# LEDArray1.net
KiCad netlist of a schematic drawn in EAGLE
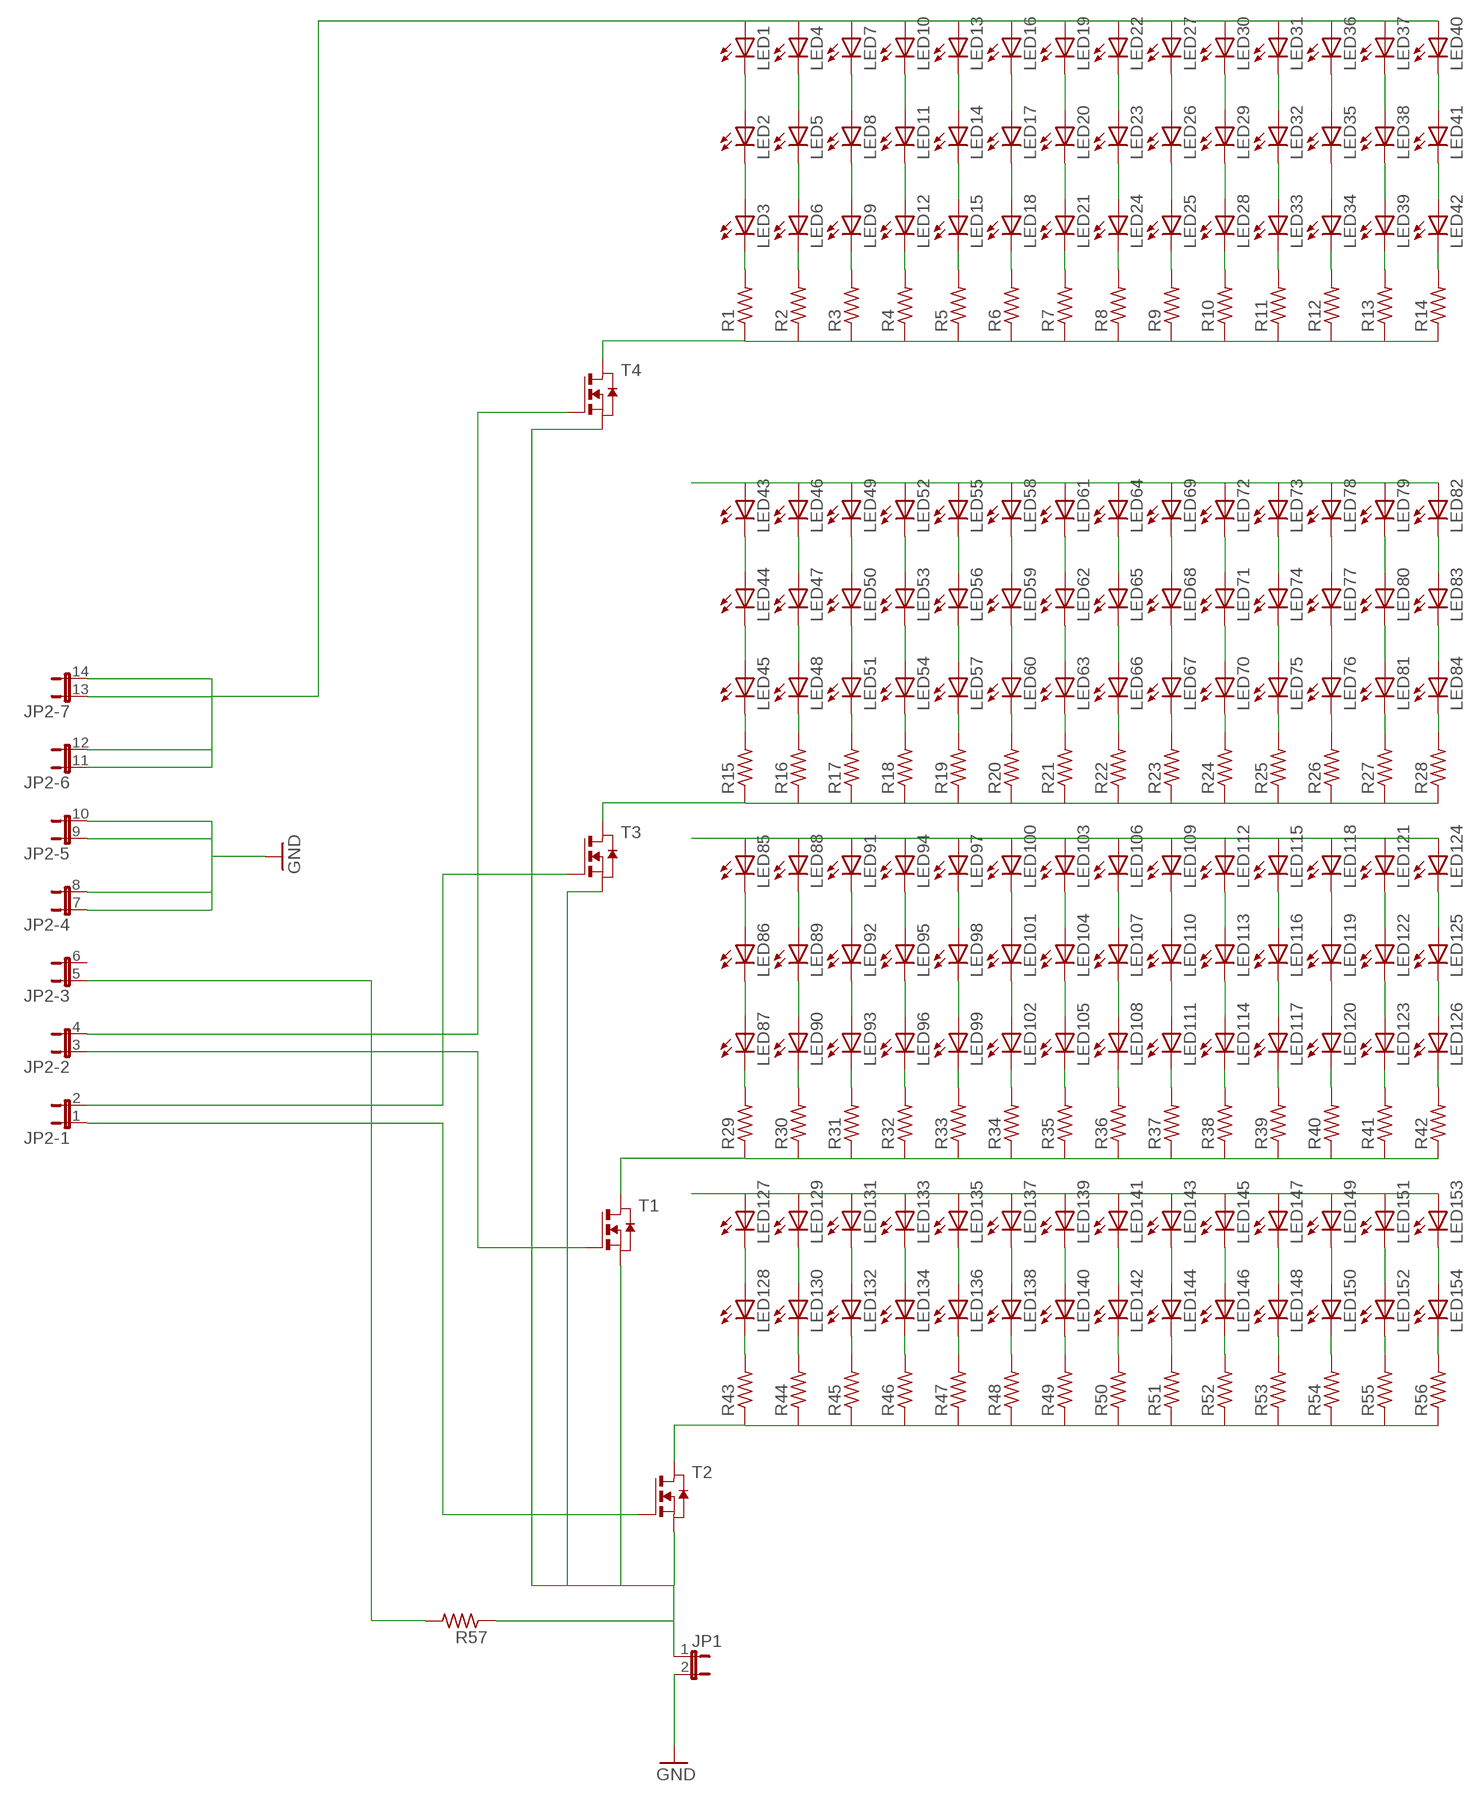
[diagram p0: schematic, sheet 1]

(export (version "E")
  (design (tool "Eeschema 10.0.6"))
  (components
    (comp (ref "JP1")
      (value "JP1E")
      (footprint "eagle-import:JP1")
      (libsource (lib "eagle-import") (part "JP1E"))
    )
    (comp (ref "JP2")
      (value "JP7QE")
      (footprint "eagle-import:JP7Q")
      (libsource (lib "eagle-import") (part "JP7QE"))
    )
    (comp (ref "LED1")
      (value "LED5MM")
      (footprint "eagle-import:LED5MM")
      (libsource (lib "eagle-import") (part "LED5MM"))
    )
    (comp (ref "LED2")
      (value "LED5MM")
      (footprint "eagle-import:LED5MM")
      (libsource (lib "eagle-import") (part "LED5MM"))
    )
    (comp (ref "LED3")
      (value "LED5MM")
      (footprint "eagle-import:LED5MM")
      (libsource (lib "eagle-import") (part "LED5MM"))
    )
    (comp (ref "LED4")
      (value "LED5MM")
      (footprint "eagle-import:LED5MM")
      (libsource (lib "eagle-import") (part "LED5MM"))
    )
    (comp (ref "LED5")
      (value "LED5MM")
      (footprint "eagle-import:LED5MM")
      (libsource (lib "eagle-import") (part "LED5MM"))
    )
    (comp (ref "LED6")
      (value "LED5MM")
      (footprint "eagle-import:LED5MM")
      (libsource (lib "eagle-import") (part "LED5MM"))
    )
    (comp (ref "LED7")
      (value "LED5MM")
      (footprint "eagle-import:LED5MM")
      (libsource (lib "eagle-import") (part "LED5MM"))
    )
    (comp (ref "LED8")
      (value "LED5MM")
      (footprint "eagle-import:LED5MM")
      (libsource (lib "eagle-import") (part "LED5MM"))
    )
    (comp (ref "LED9")
      (value "LED5MM")
      (footprint "eagle-import:LED5MM")
      (libsource (lib "eagle-import") (part "LED5MM"))
    )
    (comp (ref "LED10")
      (value "LED5MM")
      (footprint "eagle-import:LED5MM")
      (libsource (lib "eagle-import") (part "LED5MM"))
    )
    (comp (ref "LED11")
      (value "LED5MM")
      (footprint "eagle-import:LED5MM")
      (libsource (lib "eagle-import") (part "LED5MM"))
    )
    (comp (ref "LED12")
      (value "LED5MM")
      (footprint "eagle-import:LED5MM")
      (libsource (lib "eagle-import") (part "LED5MM"))
    )
    (comp (ref "LED13")
      (value "LED5MM")
      (footprint "eagle-import:LED5MM")
      (libsource (lib "eagle-import") (part "LED5MM"))
    )
    (comp (ref "LED14")
      (value "LED5MM")
      (footprint "eagle-import:LED5MM")
      (libsource (lib "eagle-import") (part "LED5MM"))
    )
    (comp (ref "LED15")
      (value "LED5MM")
      (footprint "eagle-import:LED5MM")
      (libsource (lib "eagle-import") (part "LED5MM"))
    )
    (comp (ref "LED16")
      (value "LED5MM")
      (footprint "eagle-import:LED5MM")
      (libsource (lib "eagle-import") (part "LED5MM"))
    )
    (comp (ref "LED17")
      (value "LED5MM")
      (footprint "eagle-import:LED5MM")
      (libsource (lib "eagle-import") (part "LED5MM"))
    )
    (comp (ref "LED18")
      (value "LED5MM")
      (footprint "eagle-import:LED5MM")
      (libsource (lib "eagle-import") (part "LED5MM"))
    )
    (comp (ref "LED19")
      (value "LED5MM")
      (footprint "eagle-import:LED5MM")
      (libsource (lib "eagle-import") (part "LED5MM"))
    )
    (comp (ref "LED20")
      (value "LED5MM")
      (footprint "eagle-import:LED5MM")
      (libsource (lib "eagle-import") (part "LED5MM"))
    )
    (comp (ref "LED21")
      (value "LED5MM")
      (footprint "eagle-import:LED5MM")
      (libsource (lib "eagle-import") (part "LED5MM"))
    )
    (comp (ref "LED22")
      (value "LED5MM")
      (footprint "eagle-import:LED5MM")
      (libsource (lib "eagle-import") (part "LED5MM"))
    )
    (comp (ref "LED23")
      (value "LED5MM")
      (footprint "eagle-import:LED5MM")
      (libsource (lib "eagle-import") (part "LED5MM"))
    )
    (comp (ref "LED24")
      (value "LED5MM")
      (footprint "eagle-import:LED5MM")
      (libsource (lib "eagle-import") (part "LED5MM"))
    )
    (comp (ref "LED25")
      (value "LED5MM")
      (footprint "eagle-import:LED5MM")
      (libsource (lib "eagle-import") (part "LED5MM"))
    )
    (comp (ref "LED26")
      (value "LED5MM")
      (footprint "eagle-import:LED5MM")
      (libsource (lib "eagle-import") (part "LED5MM"))
    )
    (comp (ref "LED27")
      (value "LED5MM")
      (footprint "eagle-import:LED5MM")
      (libsource (lib "eagle-import") (part "LED5MM"))
    )
    (comp (ref "LED28")
      (value "LED5MM")
      (footprint "eagle-import:LED5MM")
      (libsource (lib "eagle-import") (part "LED5MM"))
    )
    (comp (ref "LED29")
      (value "LED5MM")
      (footprint "eagle-import:LED5MM")
      (libsource (lib "eagle-import") (part "LED5MM"))
    )
    (comp (ref "LED30")
      (value "LED5MM")
      (footprint "eagle-import:LED5MM")
      (libsource (lib "eagle-import") (part "LED5MM"))
    )
    (comp (ref "LED31")
      (value "LED5MM")
      (footprint "eagle-import:LED5MM")
      (libsource (lib "eagle-import") (part "LED5MM"))
    )
    (comp (ref "LED32")
      (value "LED5MM")
      (footprint "eagle-import:LED5MM")
      (libsource (lib "eagle-import") (part "LED5MM"))
    )
    (comp (ref "LED33")
      (value "LED5MM")
      (footprint "eagle-import:LED5MM")
      (libsource (lib "eagle-import") (part "LED5MM"))
    )
    (comp (ref "LED34")
      (value "LED5MM")
      (footprint "eagle-import:LED5MM")
      (libsource (lib "eagle-import") (part "LED5MM"))
    )
    (comp (ref "LED35")
      (value "LED5MM")
      (footprint "eagle-import:LED5MM")
      (libsource (lib "eagle-import") (part "LED5MM"))
    )
    (comp (ref "LED36")
      (value "LED5MM")
      (footprint "eagle-import:LED5MM")
      (libsource (lib "eagle-import") (part "LED5MM"))
    )
    (comp (ref "LED37")
      (value "LED5MM")
      (footprint "eagle-import:LED5MM")
      (libsource (lib "eagle-import") (part "LED5MM"))
    )
    (comp (ref "LED38")
      (value "LED5MM")
      (footprint "eagle-import:LED5MM")
      (libsource (lib "eagle-import") (part "LED5MM"))
    )
    (comp (ref "LED39")
      (value "LED5MM")
      (footprint "eagle-import:LED5MM")
      (libsource (lib "eagle-import") (part "LED5MM"))
    )
    (comp (ref "LED40")
      (value "LED5MM")
      (footprint "eagle-import:LED5MM")
      (libsource (lib "eagle-import") (part "LED5MM"))
    )
    (comp (ref "LED41")
      (value "LED5MM")
      (footprint "eagle-import:LED5MM")
      (libsource (lib "eagle-import") (part "LED5MM"))
    )
    (comp (ref "LED42")
      (value "LED5MM")
      (footprint "eagle-import:LED5MM")
      (libsource (lib "eagle-import") (part "LED5MM"))
    )
    (comp (ref "LED43")
      (value "LED5MM")
      (footprint "eagle-import:LED5MM")
      (libsource (lib "eagle-import") (part "LED5MM"))
    )
    (comp (ref "LED44")
      (value "LED5MM")
      (footprint "eagle-import:LED5MM")
      (libsource (lib "eagle-import") (part "LED5MM"))
    )
    (comp (ref "LED45")
      (value "LED5MM")
      (footprint "eagle-import:LED5MM")
      (libsource (lib "eagle-import") (part "LED5MM"))
    )
    (comp (ref "LED46")
      (value "LED5MM")
      (footprint "eagle-import:LED5MM")
      (libsource (lib "eagle-import") (part "LED5MM"))
    )
    (comp (ref "LED47")
      (value "LED5MM")
      (footprint "eagle-import:LED5MM")
      (libsource (lib "eagle-import") (part "LED5MM"))
    )
    (comp (ref "LED48")
      (value "LED5MM")
      (footprint "eagle-import:LED5MM")
      (libsource (lib "eagle-import") (part "LED5MM"))
    )
    (comp (ref "LED49")
      (value "LED5MM")
      (footprint "eagle-import:LED5MM")
      (libsource (lib "eagle-import") (part "LED5MM"))
    )
    (comp (ref "LED50")
      (value "LED5MM")
      (footprint "eagle-import:LED5MM")
      (libsource (lib "eagle-import") (part "LED5MM"))
    )
    (comp (ref "LED51")
      (value "LED5MM")
      (footprint "eagle-import:LED5MM")
      (libsource (lib "eagle-import") (part "LED5MM"))
    )
    (comp (ref "LED52")
      (value "LED5MM")
      (footprint "eagle-import:LED5MM")
      (libsource (lib "eagle-import") (part "LED5MM"))
    )
    (comp (ref "LED53")
      (value "LED5MM")
      (footprint "eagle-import:LED5MM")
      (libsource (lib "eagle-import") (part "LED5MM"))
    )
    (comp (ref "LED54")
      (value "LED5MM")
      (footprint "eagle-import:LED5MM")
      (libsource (lib "eagle-import") (part "LED5MM"))
    )
    (comp (ref "LED55")
      (value "LED5MM")
      (footprint "eagle-import:LED5MM")
      (libsource (lib "eagle-import") (part "LED5MM"))
    )
    (comp (ref "LED56")
      (value "LED5MM")
      (footprint "eagle-import:LED5MM")
      (libsource (lib "eagle-import") (part "LED5MM"))
    )
    (comp (ref "LED57")
      (value "LED5MM")
      (footprint "eagle-import:LED5MM")
      (libsource (lib "eagle-import") (part "LED5MM"))
    )
    (comp (ref "LED58")
      (value "LED5MM")
      (footprint "eagle-import:LED5MM")
      (libsource (lib "eagle-import") (part "LED5MM"))
    )
    (comp (ref "LED59")
      (value "LED5MM")
      (footprint "eagle-import:LED5MM")
      (libsource (lib "eagle-import") (part "LED5MM"))
    )
    (comp (ref "LED60")
      (value "LED5MM")
      (footprint "eagle-import:LED5MM")
      (libsource (lib "eagle-import") (part "LED5MM"))
    )
    (comp (ref "LED61")
      (value "LED5MM")
      (footprint "eagle-import:LED5MM")
      (libsource (lib "eagle-import") (part "LED5MM"))
    )
    (comp (ref "LED62")
      (value "LED5MM")
      (footprint "eagle-import:LED5MM")
      (libsource (lib "eagle-import") (part "LED5MM"))
    )
    (comp (ref "LED63")
      (value "LED5MM")
      (footprint "eagle-import:LED5MM")
      (libsource (lib "eagle-import") (part "LED5MM"))
    )
    (comp (ref "LED64")
      (value "LED5MM")
      (footprint "eagle-import:LED5MM")
      (libsource (lib "eagle-import") (part "LED5MM"))
    )
    (comp (ref "LED65")
      (value "LED5MM")
      (footprint "eagle-import:LED5MM")
      (libsource (lib "eagle-import") (part "LED5MM"))
    )
    (comp (ref "LED66")
      (value "LED5MM")
      (footprint "eagle-import:LED5MM")
      (libsource (lib "eagle-import") (part "LED5MM"))
    )
    (comp (ref "LED67")
      (value "LED5MM")
      (footprint "eagle-import:LED5MM")
      (libsource (lib "eagle-import") (part "LED5MM"))
    )
    (comp (ref "LED68")
      (value "LED5MM")
      (footprint "eagle-import:LED5MM")
      (libsource (lib "eagle-import") (part "LED5MM"))
    )
    (comp (ref "LED69")
      (value "LED5MM")
      (footprint "eagle-import:LED5MM")
      (libsource (lib "eagle-import") (part "LED5MM"))
    )
    (comp (ref "LED70")
      (value "LED5MM")
      (footprint "eagle-import:LED5MM")
      (libsource (lib "eagle-import") (part "LED5MM"))
    )
    (comp (ref "LED71")
      (value "LED5MM")
      (footprint "eagle-import:LED5MM")
      (libsource (lib "eagle-import") (part "LED5MM"))
    )
    (comp (ref "LED72")
      (value "LED5MM")
      (footprint "eagle-import:LED5MM")
      (libsource (lib "eagle-import") (part "LED5MM"))
    )
    (comp (ref "LED73")
      (value "LED5MM")
      (footprint "eagle-import:LED5MM")
      (libsource (lib "eagle-import") (part "LED5MM"))
    )
    (comp (ref "LED74")
      (value "LED5MM")
      (footprint "eagle-import:LED5MM")
      (libsource (lib "eagle-import") (part "LED5MM"))
    )
    (comp (ref "LED75")
      (value "LED5MM")
      (footprint "eagle-import:LED5MM")
      (libsource (lib "eagle-import") (part "LED5MM"))
    )
    (comp (ref "LED76")
      (value "LED5MM")
      (footprint "eagle-import:LED5MM")
      (libsource (lib "eagle-import") (part "LED5MM"))
    )
    (comp (ref "LED77")
      (value "LED5MM")
      (footprint "eagle-import:LED5MM")
      (libsource (lib "eagle-import") (part "LED5MM"))
    )
    (comp (ref "LED78")
      (value "LED5MM")
      (footprint "eagle-import:LED5MM")
      (libsource (lib "eagle-import") (part "LED5MM"))
    )
    (comp (ref "LED79")
      (value "LED5MM")
      (footprint "eagle-import:LED5MM")
      (libsource (lib "eagle-import") (part "LED5MM"))
    )
    (comp (ref "LED80")
      (value "LED5MM")
      (footprint "eagle-import:LED5MM")
      (libsource (lib "eagle-import") (part "LED5MM"))
    )
    (comp (ref "LED81")
      (value "LED5MM")
      (footprint "eagle-import:LED5MM")
      (libsource (lib "eagle-import") (part "LED5MM"))
    )
    (comp (ref "LED82")
      (value "LED5MM")
      (footprint "eagle-import:LED5MM")
      (libsource (lib "eagle-import") (part "LED5MM"))
    )
    (comp (ref "LED83")
      (value "LED5MM")
      (footprint "eagle-import:LED5MM")
      (libsource (lib "eagle-import") (part "LED5MM"))
    )
    (comp (ref "LED84")
      (value "LED5MM")
      (footprint "eagle-import:LED5MM")
      (libsource (lib "eagle-import") (part "LED5MM"))
    )
    (comp (ref "LED85")
      (value "LED5MM")
      (footprint "eagle-import:LED5MM")
      (libsource (lib "eagle-import") (part "LED5MM"))
    )
    (comp (ref "LED86")
      (value "LED5MM")
      (footprint "eagle-import:LED5MM")
      (libsource (lib "eagle-import") (part "LED5MM"))
    )
    (comp (ref "LED87")
      (value "LED5MM")
      (footprint "eagle-import:LED5MM")
      (libsource (lib "eagle-import") (part "LED5MM"))
    )
    (comp (ref "LED88")
      (value "LED5MM")
      (footprint "eagle-import:LED5MM")
      (libsource (lib "eagle-import") (part "LED5MM"))
    )
    (comp (ref "LED89")
      (value "LED5MM")
      (footprint "eagle-import:LED5MM")
      (libsource (lib "eagle-import") (part "LED5MM"))
    )
    (comp (ref "LED90")
      (value "LED5MM")
      (footprint "eagle-import:LED5MM")
      (libsource (lib "eagle-import") (part "LED5MM"))
    )
    (comp (ref "LED91")
      (value "LED5MM")
      (footprint "eagle-import:LED5MM")
      (libsource (lib "eagle-import") (part "LED5MM"))
    )
    (comp (ref "LED92")
      (value "LED5MM")
      (footprint "eagle-import:LED5MM")
      (libsource (lib "eagle-import") (part "LED5MM"))
    )
    (comp (ref "LED93")
      (value "LED5MM")
      (footprint "eagle-import:LED5MM")
      (libsource (lib "eagle-import") (part "LED5MM"))
    )
    (comp (ref "LED94")
      (value "LED5MM")
      (footprint "eagle-import:LED5MM")
      (libsource (lib "eagle-import") (part "LED5MM"))
    )
    (comp (ref "LED95")
      (value "LED5MM")
      (footprint "eagle-import:LED5MM")
      (libsource (lib "eagle-import") (part "LED5MM"))
    )
    (comp (ref "LED96")
      (value "LED5MM")
      (footprint "eagle-import:LED5MM")
      (libsource (lib "eagle-import") (part "LED5MM"))
    )
    (comp (ref "LED97")
      (value "LED5MM")
      (footprint "eagle-import:LED5MM")
      (libsource (lib "eagle-import") (part "LED5MM"))
    )
    (comp (ref "LED98")
      (value "LED5MM")
      (footprint "eagle-import:LED5MM")
      (libsource (lib "eagle-import") (part "LED5MM"))
    )
    (comp (ref "LED99")
      (value "LED5MM")
      (footprint "eagle-import:LED5MM")
      (libsource (lib "eagle-import") (part "LED5MM"))
    )
    (comp (ref "LED100")
      (value "LED5MM")
      (footprint "eagle-import:LED5MM")
      (libsource (lib "eagle-import") (part "LED5MM"))
    )
    (comp (ref "LED101")
      (value "LED5MM")
      (footprint "eagle-import:LED5MM")
      (libsource (lib "eagle-import") (part "LED5MM"))
    )
    (comp (ref "LED102")
      (value "LED5MM")
      (footprint "eagle-import:LED5MM")
      (libsource (lib "eagle-import") (part "LED5MM"))
    )
    (comp (ref "LED103")
      (value "LED5MM")
      (footprint "eagle-import:LED5MM")
      (libsource (lib "eagle-import") (part "LED5MM"))
    )
    (comp (ref "LED104")
      (value "LED5MM")
      (footprint "eagle-import:LED5MM")
      (libsource (lib "eagle-import") (part "LED5MM"))
    )
    (comp (ref "LED105")
      (value "LED5MM")
      (footprint "eagle-import:LED5MM")
      (libsource (lib "eagle-import") (part "LED5MM"))
    )
    (comp (ref "LED106")
      (value "LED5MM")
      (footprint "eagle-import:LED5MM")
      (libsource (lib "eagle-import") (part "LED5MM"))
    )
    (comp (ref "LED107")
      (value "LED5MM")
      (footprint "eagle-import:LED5MM")
      (libsource (lib "eagle-import") (part "LED5MM"))
    )
    (comp (ref "LED108")
      (value "LED5MM")
      (footprint "eagle-import:LED5MM")
      (libsource (lib "eagle-import") (part "LED5MM"))
    )
    (comp (ref "LED109")
      (value "LED5MM")
      (footprint "eagle-import:LED5MM")
      (libsource (lib "eagle-import") (part "LED5MM"))
    )
    (comp (ref "LED110")
      (value "LED5MM")
      (footprint "eagle-import:LED5MM")
      (libsource (lib "eagle-import") (part "LED5MM"))
    )
    (comp (ref "LED111")
      (value "LED5MM")
      (footprint "eagle-import:LED5MM")
      (libsource (lib "eagle-import") (part "LED5MM"))
    )
    (comp (ref "LED112")
      (value "LED5MM")
      (footprint "eagle-import:LED5MM")
      (libsource (lib "eagle-import") (part "LED5MM"))
    )
    (comp (ref "LED113")
      (value "LED5MM")
      (footprint "eagle-import:LED5MM")
      (libsource (lib "eagle-import") (part "LED5MM"))
    )
    (comp (ref "LED114")
      (value "LED5MM")
      (footprint "eagle-import:LED5MM")
      (libsource (lib "eagle-import") (part "LED5MM"))
    )
    (comp (ref "LED115")
      (value "LED5MM")
      (footprint "eagle-import:LED5MM")
      (libsource (lib "eagle-import") (part "LED5MM"))
    )
    (comp (ref "LED116")
      (value "LED5MM")
      (footprint "eagle-import:LED5MM")
      (libsource (lib "eagle-import") (part "LED5MM"))
    )
    (comp (ref "LED117")
      (value "LED5MM")
      (footprint "eagle-import:LED5MM")
      (libsource (lib "eagle-import") (part "LED5MM"))
    )
    (comp (ref "LED118")
      (value "LED5MM")
      (footprint "eagle-import:LED5MM")
      (libsource (lib "eagle-import") (part "LED5MM"))
    )
    (comp (ref "LED119")
      (value "LED5MM")
      (footprint "eagle-import:LED5MM")
      (libsource (lib "eagle-import") (part "LED5MM"))
    )
    (comp (ref "LED120")
      (value "LED5MM")
      (footprint "eagle-import:LED5MM")
      (libsource (lib "eagle-import") (part "LED5MM"))
    )
    (comp (ref "LED121")
      (value "LED5MM")
      (footprint "eagle-import:LED5MM")
      (libsource (lib "eagle-import") (part "LED5MM"))
    )
    (comp (ref "LED122")
      (value "LED5MM")
      (footprint "eagle-import:LED5MM")
      (libsource (lib "eagle-import") (part "LED5MM"))
    )
    (comp (ref "LED123")
      (value "LED5MM")
      (footprint "eagle-import:LED5MM")
      (libsource (lib "eagle-import") (part "LED5MM"))
    )
    (comp (ref "LED124")
      (value "LED5MM")
      (footprint "eagle-import:LED5MM")
      (libsource (lib "eagle-import") (part "LED5MM"))
    )
    (comp (ref "LED125")
      (value "LED5MM")
      (footprint "eagle-import:LED5MM")
      (libsource (lib "eagle-import") (part "LED5MM"))
    )
    (comp (ref "LED126")
      (value "LED5MM")
      (footprint "eagle-import:LED5MM")
      (libsource (lib "eagle-import") (part "LED5MM"))
    )
    (comp (ref "LED127")
      (value "LED5MM")
      (footprint "eagle-import:LED5MM")
      (libsource (lib "eagle-import") (part "LED5MM"))
    )
    (comp (ref "LED128")
      (value "LED5MM")
      (footprint "eagle-import:LED5MM")
      (libsource (lib "eagle-import") (part "LED5MM"))
    )
    (comp (ref "LED129")
      (value "LED5MM")
      (footprint "eagle-import:LED5MM")
      (libsource (lib "eagle-import") (part "LED5MM"))
    )
    (comp (ref "LED130")
      (value "LED5MM")
      (footprint "eagle-import:LED5MM")
      (libsource (lib "eagle-import") (part "LED5MM"))
    )
    (comp (ref "LED131")
      (value "LED5MM")
      (footprint "eagle-import:LED5MM")
      (libsource (lib "eagle-import") (part "LED5MM"))
    )
    (comp (ref "LED132")
      (value "LED5MM")
      (footprint "eagle-import:LED5MM")
      (libsource (lib "eagle-import") (part "LED5MM"))
    )
    (comp (ref "LED133")
      (value "LED5MM")
      (footprint "eagle-import:LED5MM")
      (libsource (lib "eagle-import") (part "LED5MM"))
    )
    (comp (ref "LED134")
      (value "LED5MM")
      (footprint "eagle-import:LED5MM")
      (libsource (lib "eagle-import") (part "LED5MM"))
    )
    (comp (ref "LED135")
      (value "LED5MM")
      (footprint "eagle-import:LED5MM")
      (libsource (lib "eagle-import") (part "LED5MM"))
    )
    (comp (ref "LED136")
      (value "LED5MM")
      (footprint "eagle-import:LED5MM")
      (libsource (lib "eagle-import") (part "LED5MM"))
    )
    (comp (ref "LED137")
      (value "LED5MM")
      (footprint "eagle-import:LED5MM")
      (libsource (lib "eagle-import") (part "LED5MM"))
    )
    (comp (ref "LED138")
      (value "LED5MM")
      (footprint "eagle-import:LED5MM")
      (libsource (lib "eagle-import") (part "LED5MM"))
    )
    (comp (ref "LED139")
      (value "LED5MM")
      (footprint "eagle-import:LED5MM")
      (libsource (lib "eagle-import") (part "LED5MM"))
    )
    (comp (ref "LED140")
      (value "LED5MM")
      (footprint "eagle-import:LED5MM")
      (libsource (lib "eagle-import") (part "LED5MM"))
    )
    (comp (ref "LED141")
      (value "LED5MM")
      (footprint "eagle-import:LED5MM")
      (libsource (lib "eagle-import") (part "LED5MM"))
    )
    (comp (ref "LED142")
      (value "LED5MM")
      (footprint "eagle-import:LED5MM")
      (libsource (lib "eagle-import") (part "LED5MM"))
    )
    (comp (ref "LED143")
      (value "LED5MM")
      (footprint "eagle-import:LED5MM")
      (libsource (lib "eagle-import") (part "LED5MM"))
    )
    (comp (ref "LED144")
      (value "LED5MM")
      (footprint "eagle-import:LED5MM")
      (libsource (lib "eagle-import") (part "LED5MM"))
    )
    (comp (ref "LED145")
      (value "LED5MM")
      (footprint "eagle-import:LED5MM")
      (libsource (lib "eagle-import") (part "LED5MM"))
    )
    (comp (ref "LED146")
      (value "LED5MM")
      (footprint "eagle-import:LED5MM")
      (libsource (lib "eagle-import") (part "LED5MM"))
    )
    (comp (ref "LED147")
      (value "LED5MM")
      (footprint "eagle-import:LED5MM")
      (libsource (lib "eagle-import") (part "LED5MM"))
    )
    (comp (ref "LED148")
      (value "LED5MM")
      (footprint "eagle-import:LED5MM")
      (libsource (lib "eagle-import") (part "LED5MM"))
    )
    (comp (ref "LED149")
      (value "LED5MM")
      (footprint "eagle-import:LED5MM")
      (libsource (lib "eagle-import") (part "LED5MM"))
    )
    (comp (ref "LED150")
      (value "LED5MM")
      (footprint "eagle-import:LED5MM")
      (libsource (lib "eagle-import") (part "LED5MM"))
    )
    (comp (ref "LED151")
      (value "LED5MM")
      (footprint "eagle-import:LED5MM")
      (libsource (lib "eagle-import") (part "LED5MM"))
    )
    (comp (ref "LED152")
      (value "LED5MM")
      (footprint "eagle-import:LED5MM")
      (libsource (lib "eagle-import") (part "LED5MM"))
    )
    (comp (ref "LED153")
      (value "LED5MM")
      (footprint "eagle-import:LED5MM")
      (libsource (lib "eagle-import") (part "LED5MM"))
    )
    (comp (ref "LED154")
      (value "LED5MM")
      (footprint "eagle-import:LED5MM")
      (libsource (lib "eagle-import") (part "LED5MM"))
    )
    (comp (ref "R1")
      (value "R-US_R0805")
      (footprint "eagle-import:R0805")
      (libsource (lib "eagle-import") (part "R-US_R0805"))
    )
    (comp (ref "R2")
      (value "R-US_R0805")
      (footprint "eagle-import:R0805")
      (libsource (lib "eagle-import") (part "R-US_R0805"))
    )
    (comp (ref "R3")
      (value "R-US_R0805")
      (footprint "eagle-import:R0805")
      (libsource (lib "eagle-import") (part "R-US_R0805"))
    )
    (comp (ref "R4")
      (value "R-US_R0805")
      (footprint "eagle-import:R0805")
      (libsource (lib "eagle-import") (part "R-US_R0805"))
    )
    (comp (ref "R5")
      (value "R-US_R0805")
      (footprint "eagle-import:R0805")
      (libsource (lib "eagle-import") (part "R-US_R0805"))
    )
    (comp (ref "R6")
      (value "R-US_R0805")
      (footprint "eagle-import:R0805")
      (libsource (lib "eagle-import") (part "R-US_R0805"))
    )
    (comp (ref "R7")
      (value "R-US_R0805")
      (footprint "eagle-import:R0805")
      (libsource (lib "eagle-import") (part "R-US_R0805"))
    )
    (comp (ref "R8")
      (value "R-US_R0805")
      (footprint "eagle-import:R0805")
      (libsource (lib "eagle-import") (part "R-US_R0805"))
    )
    (comp (ref "R9")
      (value "R-US_R0805")
      (footprint "eagle-import:R0805")
      (libsource (lib "eagle-import") (part "R-US_R0805"))
    )
    (comp (ref "R10")
      (value "R-US_R0805")
      (footprint "eagle-import:R0805")
      (libsource (lib "eagle-import") (part "R-US_R0805"))
    )
    (comp (ref "R11")
      (value "R-US_R0805")
      (footprint "eagle-import:R0805")
      (libsource (lib "eagle-import") (part "R-US_R0805"))
    )
    (comp (ref "R12")
      (value "R-US_R0805")
      (footprint "eagle-import:R0805")
      (libsource (lib "eagle-import") (part "R-US_R0805"))
    )
    (comp (ref "R13")
      (value "R-US_R0805")
      (footprint "eagle-import:R0805")
      (libsource (lib "eagle-import") (part "R-US_R0805"))
    )
    (comp (ref "R14")
      (value "R-US_R0805")
      (footprint "eagle-import:R0805")
      (libsource (lib "eagle-import") (part "R-US_R0805"))
    )
    (comp (ref "R15")
      (value "R-US_R0805")
      (footprint "eagle-import:R0805")
      (libsource (lib "eagle-import") (part "R-US_R0805"))
    )
    (comp (ref "R16")
      (value "R-US_R0805")
      (footprint "eagle-import:R0805")
      (libsource (lib "eagle-import") (part "R-US_R0805"))
    )
    (comp (ref "R17")
      (value "R-US_R0805")
      (footprint "eagle-import:R0805")
      (libsource (lib "eagle-import") (part "R-US_R0805"))
    )
    (comp (ref "R18")
      (value "R-US_R0805")
      (footprint "eagle-import:R0805")
      (libsource (lib "eagle-import") (part "R-US_R0805"))
    )
    (comp (ref "R19")
      (value "R-US_R0805")
      (footprint "eagle-import:R0805")
      (libsource (lib "eagle-import") (part "R-US_R0805"))
    )
    (comp (ref "R20")
      (value "R-US_R0805")
      (footprint "eagle-import:R0805")
      (libsource (lib "eagle-import") (part "R-US_R0805"))
    )
    (comp (ref "R21")
      (value "R-US_R0805")
      (footprint "eagle-import:R0805")
      (libsource (lib "eagle-import") (part "R-US_R0805"))
    )
    (comp (ref "R22")
      (value "R-US_R0805")
      (footprint "eagle-import:R0805")
      (libsource (lib "eagle-import") (part "R-US_R0805"))
    )
    (comp (ref "R23")
      (value "R-US_R0805")
      (footprint "eagle-import:R0805")
      (libsource (lib "eagle-import") (part "R-US_R0805"))
    )
    (comp (ref "R24")
      (value "R-US_R0805")
      (footprint "eagle-import:R0805")
      (libsource (lib "eagle-import") (part "R-US_R0805"))
    )
    (comp (ref "R25")
      (value "R-US_R0805")
      (footprint "eagle-import:R0805")
      (libsource (lib "eagle-import") (part "R-US_R0805"))
    )
    (comp (ref "R26")
      (value "R-US_R0805")
      (footprint "eagle-import:R0805")
      (libsource (lib "eagle-import") (part "R-US_R0805"))
    )
    (comp (ref "R27")
      (value "R-US_R0805")
      (footprint "eagle-import:R0805")
      (libsource (lib "eagle-import") (part "R-US_R0805"))
    )
    (comp (ref "R28")
      (value "R-US_R0805")
      (footprint "eagle-import:R0805")
      (libsource (lib "eagle-import") (part "R-US_R0805"))
    )
    (comp (ref "R29")
      (value "R-US_R0805")
      (footprint "eagle-import:R0805")
      (libsource (lib "eagle-import") (part "R-US_R0805"))
    )
    (comp (ref "R30")
      (value "R-US_R0805")
      (footprint "eagle-import:R0805")
      (libsource (lib "eagle-import") (part "R-US_R0805"))
    )
    (comp (ref "R31")
      (value "R-US_R0805")
      (footprint "eagle-import:R0805")
      (libsource (lib "eagle-import") (part "R-US_R0805"))
    )
    (comp (ref "R32")
      (value "R-US_R0805")
      (footprint "eagle-import:R0805")
      (libsource (lib "eagle-import") (part "R-US_R0805"))
    )
    (comp (ref "R33")
      (value "R-US_R0805")
      (footprint "eagle-import:R0805")
      (libsource (lib "eagle-import") (part "R-US_R0805"))
    )
    (comp (ref "R34")
      (value "R-US_R0805")
      (footprint "eagle-import:R0805")
      (libsource (lib "eagle-import") (part "R-US_R0805"))
    )
    (comp (ref "R35")
      (value "R-US_R0805")
      (footprint "eagle-import:R0805")
      (libsource (lib "eagle-import") (part "R-US_R0805"))
    )
    (comp (ref "R36")
      (value "R-US_R0805")
      (footprint "eagle-import:R0805")
      (libsource (lib "eagle-import") (part "R-US_R0805"))
    )
    (comp (ref "R37")
      (value "R-US_R0805")
      (footprint "eagle-import:R0805")
      (libsource (lib "eagle-import") (part "R-US_R0805"))
    )
    (comp (ref "R38")
      (value "R-US_R0805")
      (footprint "eagle-import:R0805")
      (libsource (lib "eagle-import") (part "R-US_R0805"))
    )
    (comp (ref "R39")
      (value "R-US_R0805")
      (footprint "eagle-import:R0805")
      (libsource (lib "eagle-import") (part "R-US_R0805"))
    )
    (comp (ref "R40")
      (value "R-US_R0805")
      (footprint "eagle-import:R0805")
      (libsource (lib "eagle-import") (part "R-US_R0805"))
    )
    (comp (ref "R41")
      (value "R-US_R0805")
      (footprint "eagle-import:R0805")
      (libsource (lib "eagle-import") (part "R-US_R0805"))
    )
    (comp (ref "R42")
      (value "R-US_R0805")
      (footprint "eagle-import:R0805")
      (libsource (lib "eagle-import") (part "R-US_R0805"))
    )
    (comp (ref "R43")
      (value "R-US_R0805")
      (footprint "eagle-import:R0805")
      (libsource (lib "eagle-import") (part "R-US_R0805"))
    )
    (comp (ref "R44")
      (value "R-US_R0805")
      (footprint "eagle-import:R0805")
      (libsource (lib "eagle-import") (part "R-US_R0805"))
    )
    (comp (ref "R45")
      (value "R-US_R0805")
      (footprint "eagle-import:R0805")
      (libsource (lib "eagle-import") (part "R-US_R0805"))
    )
    (comp (ref "R46")
      (value "R-US_R0805")
      (footprint "eagle-import:R0805")
      (libsource (lib "eagle-import") (part "R-US_R0805"))
    )
    (comp (ref "R47")
      (value "R-US_R0805")
      (footprint "eagle-import:R0805")
      (libsource (lib "eagle-import") (part "R-US_R0805"))
    )
    (comp (ref "R48")
      (value "R-US_R0805")
      (footprint "eagle-import:R0805")
      (libsource (lib "eagle-import") (part "R-US_R0805"))
    )
    (comp (ref "R49")
      (value "R-US_R0805")
      (footprint "eagle-import:R0805")
      (libsource (lib "eagle-import") (part "R-US_R0805"))
    )
    (comp (ref "R50")
      (value "R-US_R0805")
      (footprint "eagle-import:R0805")
      (libsource (lib "eagle-import") (part "R-US_R0805"))
    )
    (comp (ref "R51")
      (value "R-US_R0805")
      (footprint "eagle-import:R0805")
      (libsource (lib "eagle-import") (part "R-US_R0805"))
    )
    (comp (ref "R52")
      (value "R-US_R0805")
      (footprint "eagle-import:R0805")
      (libsource (lib "eagle-import") (part "R-US_R0805"))
    )
    (comp (ref "R53")
      (value "R-US_R0805")
      (footprint "eagle-import:R0805")
      (libsource (lib "eagle-import") (part "R-US_R0805"))
    )
    (comp (ref "R54")
      (value "R-US_R0805")
      (footprint "eagle-import:R0805")
      (libsource (lib "eagle-import") (part "R-US_R0805"))
    )
    (comp (ref "R55")
      (value "R-US_R0805")
      (footprint "eagle-import:R0805")
      (libsource (lib "eagle-import") (part "R-US_R0805"))
    )
    (comp (ref "R56")
      (value "R-US_R0805")
      (footprint "eagle-import:R0805")
      (libsource (lib "eagle-import") (part "R-US_R0805"))
    )
    (comp (ref "R57")
      (value "R-US_R0805")
      (footprint "eagle-import:R0805")
      (libsource (lib "eagle-import") (part "R-US_R0805"))
    )
    (comp (ref "T1")
      (value "NMOSSOT23")
      (footprint "eagle-import:SOT-23")
      (libsource (lib "eagle-import") (part "NMOSSOT23"))
    )
    (comp (ref "T2")
      (value "NMOSSOT23")
      (footprint "eagle-import:SOT-23")
      (libsource (lib "eagle-import") (part "NMOSSOT23"))
    )
    (comp (ref "T3")
      (value "NMOSSOT23")
      (footprint "eagle-import:SOT-23")
      (libsource (lib "eagle-import") (part "NMOSSOT23"))
    )
    (comp (ref "T4")
      (value "NMOSSOT23")
      (footprint "eagle-import:SOT-23")
      (libsource (lib "eagle-import") (part "NMOSSOT23"))
    )
  )
  (nets
    (net (code "1") (name "/VCC") (class "Default")
      (node (ref "JP2") (pin "11") (pinfunction "1_11") (pintype "passive"))
      (node (ref "JP2") (pin "12") (pinfunction "2_12") (pintype "passive"))
      (node (ref "JP2") (pin "13") (pinfunction "1_13") (pintype "passive"))
      (node (ref "JP2") (pin "14") (pinfunction "2_14") (pintype "passive"))
      (node (ref "LED1") (pin "A") (pinfunction "A_A") (pintype "passive"))
      (node (ref "LED10") (pin "A") (pinfunction "A_A") (pintype "passive"))
      (node (ref "LED100") (pin "A") (pinfunction "A_A") (pintype "passive"))
      (node (ref "LED103") (pin "A") (pinfunction "A_A") (pintype "passive"))
      (node (ref "LED106") (pin "A") (pinfunction "A_A") (pintype "passive"))
      (node (ref "LED109") (pin "A") (pinfunction "A_A") (pintype "passive"))
      (node (ref "LED112") (pin "A") (pinfunction "A_A") (pintype "passive"))
      (node (ref "LED115") (pin "A") (pinfunction "A_A") (pintype "passive"))
      (node (ref "LED118") (pin "A") (pinfunction "A_A") (pintype "passive"))
      (node (ref "LED121") (pin "A") (pinfunction "A_A") (pintype "passive"))
      (node (ref "LED124") (pin "A") (pinfunction "A_A") (pintype "passive"))
      (node (ref "LED127") (pin "A") (pinfunction "A_A") (pintype "passive"))
      (node (ref "LED129") (pin "A") (pinfunction "A_A") (pintype "passive"))
      (node (ref "LED13") (pin "A") (pinfunction "A_A") (pintype "passive"))
      (node (ref "LED131") (pin "A") (pinfunction "A_A") (pintype "passive"))
      (node (ref "LED133") (pin "A") (pinfunction "A_A") (pintype "passive"))
      (node (ref "LED135") (pin "A") (pinfunction "A_A") (pintype "passive"))
      (node (ref "LED137") (pin "A") (pinfunction "A_A") (pintype "passive"))
      (node (ref "LED139") (pin "A") (pinfunction "A_A") (pintype "passive"))
      (node (ref "LED141") (pin "A") (pinfunction "A_A") (pintype "passive"))
      (node (ref "LED143") (pin "A") (pinfunction "A_A") (pintype "passive"))
      (node (ref "LED145") (pin "A") (pinfunction "A_A") (pintype "passive"))
      (node (ref "LED147") (pin "A") (pinfunction "A_A") (pintype "passive"))
      (node (ref "LED149") (pin "A") (pinfunction "A_A") (pintype "passive"))
      (node (ref "LED151") (pin "A") (pinfunction "A_A") (pintype "passive"))
      (node (ref "LED153") (pin "A") (pinfunction "A_A") (pintype "passive"))
      (node (ref "LED16") (pin "A") (pinfunction "A_A") (pintype "passive"))
      (node (ref "LED19") (pin "A") (pinfunction "A_A") (pintype "passive"))
      (node (ref "LED22") (pin "A") (pinfunction "A_A") (pintype "passive"))
      (node (ref "LED27") (pin "A") (pinfunction "A_A") (pintype "passive"))
      (node (ref "LED30") (pin "A") (pinfunction "A_A") (pintype "passive"))
      (node (ref "LED31") (pin "A") (pinfunction "A_A") (pintype "passive"))
      (node (ref "LED36") (pin "A") (pinfunction "A_A") (pintype "passive"))
      (node (ref "LED37") (pin "A") (pinfunction "A_A") (pintype "passive"))
      (node (ref "LED4") (pin "A") (pinfunction "A_A") (pintype "passive"))
      (node (ref "LED40") (pin "A") (pinfunction "A_A") (pintype "passive"))
      (node (ref "LED43") (pin "A") (pinfunction "A_A") (pintype "passive"))
      (node (ref "LED46") (pin "A") (pinfunction "A_A") (pintype "passive"))
      (node (ref "LED49") (pin "A") (pinfunction "A_A") (pintype "passive"))
      (node (ref "LED52") (pin "A") (pinfunction "A_A") (pintype "passive"))
      (node (ref "LED55") (pin "A") (pinfunction "A_A") (pintype "passive"))
      (node (ref "LED58") (pin "A") (pinfunction "A_A") (pintype "passive"))
      (node (ref "LED61") (pin "A") (pinfunction "A_A") (pintype "passive"))
      (node (ref "LED64") (pin "A") (pinfunction "A_A") (pintype "passive"))
      (node (ref "LED69") (pin "A") (pinfunction "A_A") (pintype "passive"))
      (node (ref "LED7") (pin "A") (pinfunction "A_A") (pintype "passive"))
      (node (ref "LED72") (pin "A") (pinfunction "A_A") (pintype "passive"))
      (node (ref "LED73") (pin "A") (pinfunction "A_A") (pintype "passive"))
      (node (ref "LED78") (pin "A") (pinfunction "A_A") (pintype "passive"))
      (node (ref "LED79") (pin "A") (pinfunction "A_A") (pintype "passive"))
      (node (ref "LED82") (pin "A") (pinfunction "A_A") (pintype "passive"))
      (node (ref "LED85") (pin "A") (pinfunction "A_A") (pintype "passive"))
      (node (ref "LED88") (pin "A") (pinfunction "A_A") (pintype "passive"))
      (node (ref "LED91") (pin "A") (pinfunction "A_A") (pintype "passive"))
      (node (ref "LED94") (pin "A") (pinfunction "A_A") (pintype "passive"))
      (node (ref "LED97") (pin "A") (pinfunction "A_A") (pintype "passive"))
    )
    (net (code "2") (name "GND") (class "Default")
      (node (ref "JP1") (pin "2") (pinfunction "2_2") (pintype "passive"))
      (node (ref "JP2") (pin "10") (pinfunction "2_10") (pintype "passive"))
      (node (ref "JP2") (pin "7") (pinfunction "1_7") (pintype "passive"))
      (node (ref "JP2") (pin "8") (pinfunction "2_8") (pintype "passive"))
      (node (ref "JP2") (pin "9") (pinfunction "1_9") (pintype "passive"))
    )
    (net (code "3") (name "Net-(JP2B-1)") (class "Default")
      (node (ref "JP2") (pin "3") (pinfunction "1_3") (pintype "passive"))
      (node (ref "T1") (pin "3") (pinfunction "G_3") (pintype "passive"))
    )
    (net (code "4") (name "Net-(JP2B-2)") (class "Default")
      (node (ref "JP2") (pin "4") (pinfunction "2_4") (pintype "passive"))
      (node (ref "T4") (pin "3") (pinfunction "G_3") (pintype "passive"))
    )
    (net (code "5") (name "Net-(JP2C-1)") (class "Default")
      (node (ref "JP2") (pin "5") (pinfunction "1_5") (pintype "passive"))
      (node (ref "R57") (pin "2") (pinfunction "2_2") (pintype "passive"))
    )
    (net (code "6") (name "Net-(LED1-C)") (class "Default")
      (node (ref "LED1") (pin "K") (pinfunction "C_K") (pintype "passive"))
      (node (ref "LED2") (pin "A") (pinfunction "A_A") (pintype "passive"))
    )
    (net (code "7") (name "Net-(LED2-C)") (class "Default")
      (node (ref "LED2") (pin "K") (pinfunction "C_K") (pintype "passive"))
      (node (ref "LED3") (pin "A") (pinfunction "A_A") (pintype "passive"))
    )
    (net (code "8") (name "Net-(LED3-C)") (class "Default")
      (node (ref "LED3") (pin "K") (pinfunction "C_K") (pintype "passive"))
      (node (ref "R1") (pin "2") (pinfunction "2_2") (pintype "passive"))
    )
    (net (code "9") (name "Net-(LED4-C)") (class "Default")
      (node (ref "LED4") (pin "K") (pinfunction "C_K") (pintype "passive"))
      (node (ref "LED5") (pin "A") (pinfunction "A_A") (pintype "passive"))
    )
    (net (code "10") (name "Net-(LED5-C)") (class "Default")
      (node (ref "LED5") (pin "K") (pinfunction "C_K") (pintype "passive"))
      (node (ref "LED6") (pin "A") (pinfunction "A_A") (pintype "passive"))
    )
    (net (code "11") (name "Net-(LED6-C)") (class "Default")
      (node (ref "LED6") (pin "K") (pinfunction "C_K") (pintype "passive"))
      (node (ref "R2") (pin "2") (pinfunction "2_2") (pintype "passive"))
    )
    (net (code "12") (name "Net-(LED7-C)") (class "Default")
      (node (ref "LED7") (pin "K") (pinfunction "C_K") (pintype "passive"))
      (node (ref "LED8") (pin "A") (pinfunction "A_A") (pintype "passive"))
    )
    (net (code "13") (name "Net-(LED8-C)") (class "Default")
      (node (ref "LED8") (pin "K") (pinfunction "C_K") (pintype "passive"))
      (node (ref "LED9") (pin "A") (pinfunction "A_A") (pintype "passive"))
    )
    (net (code "14") (name "Net-(LED9-C)") (class "Default")
      (node (ref "LED9") (pin "K") (pinfunction "C_K") (pintype "passive"))
      (node (ref "R3") (pin "2") (pinfunction "2_2") (pintype "passive"))
    )
    (net (code "15") (name "Net-(LED10-C)") (class "Default")
      (node (ref "LED10") (pin "K") (pinfunction "C_K") (pintype "passive"))
      (node (ref "LED11") (pin "A") (pinfunction "A_A") (pintype "passive"))
    )
    (net (code "16") (name "Net-(LED11-C)") (class "Default")
      (node (ref "LED11") (pin "K") (pinfunction "C_K") (pintype "passive"))
      (node (ref "LED12") (pin "A") (pinfunction "A_A") (pintype "passive"))
    )
    (net (code "17") (name "Net-(LED12-C)") (class "Default")
      (node (ref "LED12") (pin "K") (pinfunction "C_K") (pintype "passive"))
      (node (ref "R4") (pin "2") (pinfunction "2_2") (pintype "passive"))
    )
    (net (code "18") (name "Net-(LED13-C)") (class "Default")
      (node (ref "LED13") (pin "K") (pinfunction "C_K") (pintype "passive"))
      (node (ref "LED14") (pin "A") (pinfunction "A_A") (pintype "passive"))
    )
    (net (code "19") (name "Net-(LED14-C)") (class "Default")
      (node (ref "LED14") (pin "K") (pinfunction "C_K") (pintype "passive"))
      (node (ref "LED15") (pin "A") (pinfunction "A_A") (pintype "passive"))
    )
    (net (code "20") (name "Net-(LED15-C)") (class "Default")
      (node (ref "LED15") (pin "K") (pinfunction "C_K") (pintype "passive"))
      (node (ref "R5") (pin "2") (pinfunction "2_2") (pintype "passive"))
    )
    (net (code "21") (name "Net-(LED16-C)") (class "Default")
      (node (ref "LED16") (pin "K") (pinfunction "C_K") (pintype "passive"))
      (node (ref "LED17") (pin "A") (pinfunction "A_A") (pintype "passive"))
    )
    (net (code "22") (name "Net-(LED17-C)") (class "Default")
      (node (ref "LED17") (pin "K") (pinfunction "C_K") (pintype "passive"))
      (node (ref "LED18") (pin "A") (pinfunction "A_A") (pintype "passive"))
    )
    (net (code "23") (name "Net-(LED18-C)") (class "Default")
      (node (ref "LED18") (pin "K") (pinfunction "C_K") (pintype "passive"))
      (node (ref "R6") (pin "2") (pinfunction "2_2") (pintype "passive"))
    )
    (net (code "24") (name "Net-(LED19-C)") (class "Default")
      (node (ref "LED19") (pin "K") (pinfunction "C_K") (pintype "passive"))
      (node (ref "LED20") (pin "A") (pinfunction "A_A") (pintype "passive"))
    )
    (net (code "25") (name "Net-(LED20-C)") (class "Default")
      (node (ref "LED20") (pin "K") (pinfunction "C_K") (pintype "passive"))
      (node (ref "LED21") (pin "A") (pinfunction "A_A") (pintype "passive"))
    )
    (net (code "26") (name "Net-(LED21-C)") (class "Default")
      (node (ref "LED21") (pin "K") (pinfunction "C_K") (pintype "passive"))
      (node (ref "R7") (pin "2") (pinfunction "2_2") (pintype "passive"))
    )
    (net (code "27") (name "Net-(LED22-C)") (class "Default")
      (node (ref "LED22") (pin "K") (pinfunction "C_K") (pintype "passive"))
      (node (ref "LED23") (pin "A") (pinfunction "A_A") (pintype "passive"))
    )
    (net (code "28") (name "Net-(LED23-C)") (class "Default")
      (node (ref "LED23") (pin "K") (pinfunction "C_K") (pintype "passive"))
      (node (ref "LED24") (pin "A") (pinfunction "A_A") (pintype "passive"))
    )
    (net (code "29") (name "Net-(LED24-C)") (class "Default")
      (node (ref "LED24") (pin "K") (pinfunction "C_K") (pintype "passive"))
      (node (ref "R8") (pin "2") (pinfunction "2_2") (pintype "passive"))
    )
    (net (code "30") (name "Net-(LED25-C)") (class "Default")
      (node (ref "LED25") (pin "K") (pinfunction "C_K") (pintype "passive"))
      (node (ref "R9") (pin "2") (pinfunction "2_2") (pintype "passive"))
    )
    (net (code "31") (name "Net-(LED26-C)") (class "Default")
      (node (ref "LED25") (pin "A") (pinfunction "A_A") (pintype "passive"))
      (node (ref "LED26") (pin "K") (pinfunction "C_K") (pintype "passive"))
    )
    (net (code "32") (name "Net-(LED27-C)") (class "Default")
      (node (ref "LED26") (pin "A") (pinfunction "A_A") (pintype "passive"))
      (node (ref "LED27") (pin "K") (pinfunction "C_K") (pintype "passive"))
    )
    (net (code "33") (name "Net-(LED28-C)") (class "Default")
      (node (ref "LED28") (pin "K") (pinfunction "C_K") (pintype "passive"))
      (node (ref "R10") (pin "2") (pinfunction "2_2") (pintype "passive"))
    )
    (net (code "34") (name "Net-(LED29-C)") (class "Default")
      (node (ref "LED28") (pin "A") (pinfunction "A_A") (pintype "passive"))
      (node (ref "LED29") (pin "K") (pinfunction "C_K") (pintype "passive"))
    )
    (net (code "35") (name "Net-(LED30-C)") (class "Default")
      (node (ref "LED29") (pin "A") (pinfunction "A_A") (pintype "passive"))
      (node (ref "LED30") (pin "K") (pinfunction "C_K") (pintype "passive"))
    )
    (net (code "36") (name "Net-(LED31-C)") (class "Default")
      (node (ref "LED31") (pin "K") (pinfunction "C_K") (pintype "passive"))
      (node (ref "LED32") (pin "A") (pinfunction "A_A") (pintype "passive"))
    )
    (net (code "37") (name "Net-(LED32-C)") (class "Default")
      (node (ref "LED32") (pin "K") (pinfunction "C_K") (pintype "passive"))
      (node (ref "LED33") (pin "A") (pinfunction "A_A") (pintype "passive"))
    )
    (net (code "38") (name "Net-(LED33-C)") (class "Default")
      (node (ref "LED33") (pin "K") (pinfunction "C_K") (pintype "passive"))
      (node (ref "R11") (pin "2") (pinfunction "2_2") (pintype "passive"))
    )
    (net (code "39") (name "Net-(LED34-C)") (class "Default")
      (node (ref "LED34") (pin "K") (pinfunction "C_K") (pintype "passive"))
      (node (ref "R12") (pin "2") (pinfunction "2_2") (pintype "passive"))
    )
    (net (code "40") (name "Net-(LED35-C)") (class "Default")
      (node (ref "LED34") (pin "A") (pinfunction "A_A") (pintype "passive"))
      (node (ref "LED35") (pin "K") (pinfunction "C_K") (pintype "passive"))
    )
    (net (code "41") (name "Net-(LED36-C)") (class "Default")
      (node (ref "LED35") (pin "A") (pinfunction "A_A") (pintype "passive"))
      (node (ref "LED36") (pin "K") (pinfunction "C_K") (pintype "passive"))
    )
    (net (code "42") (name "Net-(LED37-C)") (class "Default")
      (node (ref "LED37") (pin "K") (pinfunction "C_K") (pintype "passive"))
      (node (ref "LED38") (pin "A") (pinfunction "A_A") (pintype "passive"))
    )
    (net (code "43") (name "Net-(LED38-C)") (class "Default")
      (node (ref "LED38") (pin "K") (pinfunction "C_K") (pintype "passive"))
      (node (ref "LED39") (pin "A") (pinfunction "A_A") (pintype "passive"))
    )
    (net (code "44") (name "Net-(LED39-C)") (class "Default")
      (node (ref "LED39") (pin "K") (pinfunction "C_K") (pintype "passive"))
      (node (ref "R13") (pin "2") (pinfunction "2_2") (pintype "passive"))
    )
    (net (code "45") (name "Net-(LED40-C)") (class "Default")
      (node (ref "LED40") (pin "K") (pinfunction "C_K") (pintype "passive"))
      (node (ref "LED41") (pin "A") (pinfunction "A_A") (pintype "passive"))
    )
    (net (code "46") (name "Net-(LED41-C)") (class "Default")
      (node (ref "LED41") (pin "K") (pinfunction "C_K") (pintype "passive"))
      (node (ref "LED42") (pin "A") (pinfunction "A_A") (pintype "passive"))
    )
    (net (code "47") (name "Net-(LED42-C)") (class "Default")
      (node (ref "LED42") (pin "K") (pinfunction "C_K") (pintype "passive"))
      (node (ref "R14") (pin "2") (pinfunction "2_2") (pintype "passive"))
    )
    (net (code "48") (name "Net-(LED43-C)") (class "Default")
      (node (ref "LED43") (pin "K") (pinfunction "C_K") (pintype "passive"))
      (node (ref "LED44") (pin "A") (pinfunction "A_A") (pintype "passive"))
    )
    (net (code "49") (name "Net-(LED44-C)") (class "Default")
      (node (ref "LED44") (pin "K") (pinfunction "C_K") (pintype "passive"))
      (node (ref "LED45") (pin "A") (pinfunction "A_A") (pintype "passive"))
    )
    (net (code "50") (name "Net-(LED45-C)") (class "Default")
      (node (ref "LED45") (pin "K") (pinfunction "C_K") (pintype "passive"))
      (node (ref "R15") (pin "2") (pinfunction "2_2") (pintype "passive"))
    )
    (net (code "51") (name "Net-(LED46-C)") (class "Default")
      (node (ref "LED46") (pin "K") (pinfunction "C_K") (pintype "passive"))
      (node (ref "LED47") (pin "A") (pinfunction "A_A") (pintype "passive"))
    )
    (net (code "52") (name "Net-(LED47-C)") (class "Default")
      (node (ref "LED47") (pin "K") (pinfunction "C_K") (pintype "passive"))
      (node (ref "LED48") (pin "A") (pinfunction "A_A") (pintype "passive"))
    )
    (net (code "53") (name "Net-(LED48-C)") (class "Default")
      (node (ref "LED48") (pin "K") (pinfunction "C_K") (pintype "passive"))
      (node (ref "R16") (pin "2") (pinfunction "2_2") (pintype "passive"))
    )
    (net (code "54") (name "Net-(LED49-C)") (class "Default")
      (node (ref "LED49") (pin "K") (pinfunction "C_K") (pintype "passive"))
      (node (ref "LED50") (pin "A") (pinfunction "A_A") (pintype "passive"))
    )
    (net (code "55") (name "Net-(LED50-C)") (class "Default")
      (node (ref "LED50") (pin "K") (pinfunction "C_K") (pintype "passive"))
      (node (ref "LED51") (pin "A") (pinfunction "A_A") (pintype "passive"))
    )
    (net (code "56") (name "Net-(LED51-C)") (class "Default")
      (node (ref "LED51") (pin "K") (pinfunction "C_K") (pintype "passive"))
      (node (ref "R17") (pin "2") (pinfunction "2_2") (pintype "passive"))
    )
    (net (code "57") (name "Net-(LED52-C)") (class "Default")
      (node (ref "LED52") (pin "K") (pinfunction "C_K") (pintype "passive"))
      (node (ref "LED53") (pin "A") (pinfunction "A_A") (pintype "passive"))
    )
    (net (code "58") (name "Net-(LED53-C)") (class "Default")
      (node (ref "LED53") (pin "K") (pinfunction "C_K") (pintype "passive"))
      (node (ref "LED54") (pin "A") (pinfunction "A_A") (pintype "passive"))
    )
    (net (code "59") (name "Net-(LED54-C)") (class "Default")
      (node (ref "LED54") (pin "K") (pinfunction "C_K") (pintype "passive"))
      (node (ref "R18") (pin "2") (pinfunction "2_2") (pintype "passive"))
    )
    (net (code "60") (name "Net-(LED55-C)") (class "Default")
      (node (ref "LED55") (pin "K") (pinfunction "C_K") (pintype "passive"))
      (node (ref "LED56") (pin "A") (pinfunction "A_A") (pintype "passive"))
    )
    (net (code "61") (name "Net-(LED56-C)") (class "Default")
      (node (ref "LED56") (pin "K") (pinfunction "C_K") (pintype "passive"))
      (node (ref "LED57") (pin "A") (pinfunction "A_A") (pintype "passive"))
    )
    (net (code "62") (name "Net-(LED57-C)") (class "Default")
      (node (ref "LED57") (pin "K") (pinfunction "C_K") (pintype "passive"))
      (node (ref "R19") (pin "2") (pinfunction "2_2") (pintype "passive"))
    )
    (net (code "63") (name "Net-(LED58-C)") (class "Default")
      (node (ref "LED58") (pin "K") (pinfunction "C_K") (pintype "passive"))
      (node (ref "LED59") (pin "A") (pinfunction "A_A") (pintype "passive"))
    )
    (net (code "64") (name "Net-(LED59-C)") (class "Default")
      (node (ref "LED59") (pin "K") (pinfunction "C_K") (pintype "passive"))
      (node (ref "LED60") (pin "A") (pinfunction "A_A") (pintype "passive"))
    )
    (net (code "65") (name "Net-(LED60-C)") (class "Default")
      (node (ref "LED60") (pin "K") (pinfunction "C_K") (pintype "passive"))
      (node (ref "R20") (pin "2") (pinfunction "2_2") (pintype "passive"))
    )
    (net (code "66") (name "Net-(LED61-C)") (class "Default")
      (node (ref "LED61") (pin "K") (pinfunction "C_K") (pintype "passive"))
      (node (ref "LED62") (pin "A") (pinfunction "A_A") (pintype "passive"))
    )
    (net (code "67") (name "Net-(LED62-C)") (class "Default")
      (node (ref "LED62") (pin "K") (pinfunction "C_K") (pintype "passive"))
      (node (ref "LED63") (pin "A") (pinfunction "A_A") (pintype "passive"))
    )
    (net (code "68") (name "Net-(LED63-C)") (class "Default")
      (node (ref "LED63") (pin "K") (pinfunction "C_K") (pintype "passive"))
      (node (ref "R21") (pin "2") (pinfunction "2_2") (pintype "passive"))
    )
    (net (code "69") (name "Net-(LED64-C)") (class "Default")
      (node (ref "LED64") (pin "K") (pinfunction "C_K") (pintype "passive"))
      (node (ref "LED65") (pin "A") (pinfunction "A_A") (pintype "passive"))
    )
    (net (code "70") (name "Net-(LED65-C)") (class "Default")
      (node (ref "LED65") (pin "K") (pinfunction "C_K") (pintype "passive"))
      (node (ref "LED66") (pin "A") (pinfunction "A_A") (pintype "passive"))
    )
    (net (code "71") (name "Net-(LED66-C)") (class "Default")
      (node (ref "LED66") (pin "K") (pinfunction "C_K") (pintype "passive"))
      (node (ref "R22") (pin "2") (pinfunction "2_2") (pintype "passive"))
    )
    (net (code "72") (name "Net-(LED67-C)") (class "Default")
      (node (ref "LED67") (pin "K") (pinfunction "C_K") (pintype "passive"))
      (node (ref "R23") (pin "2") (pinfunction "2_2") (pintype "passive"))
    )
    (net (code "73") (name "Net-(LED68-C)") (class "Default")
      (node (ref "LED67") (pin "A") (pinfunction "A_A") (pintype "passive"))
      (node (ref "LED68") (pin "K") (pinfunction "C_K") (pintype "passive"))
    )
    (net (code "74") (name "Net-(LED69-C)") (class "Default")
      (node (ref "LED68") (pin "A") (pinfunction "A_A") (pintype "passive"))
      (node (ref "LED69") (pin "K") (pinfunction "C_K") (pintype "passive"))
    )
    (net (code "75") (name "Net-(LED70-C)") (class "Default")
      (node (ref "LED70") (pin "K") (pinfunction "C_K") (pintype "passive"))
      (node (ref "R24") (pin "2") (pinfunction "2_2") (pintype "passive"))
    )
    (net (code "76") (name "Net-(LED71-C)") (class "Default")
      (node (ref "LED70") (pin "A") (pinfunction "A_A") (pintype "passive"))
      (node (ref "LED71") (pin "K") (pinfunction "C_K") (pintype "passive"))
    )
    (net (code "77") (name "Net-(LED72-C)") (class "Default")
      (node (ref "LED71") (pin "A") (pinfunction "A_A") (pintype "passive"))
      (node (ref "LED72") (pin "K") (pinfunction "C_K") (pintype "passive"))
    )
    (net (code "78") (name "Net-(LED73-C)") (class "Default")
      (node (ref "LED73") (pin "K") (pinfunction "C_K") (pintype "passive"))
      (node (ref "LED74") (pin "A") (pinfunction "A_A") (pintype "passive"))
    )
    (net (code "79") (name "Net-(LED74-C)") (class "Default")
      (node (ref "LED74") (pin "K") (pinfunction "C_K") (pintype "passive"))
      (node (ref "LED75") (pin "A") (pinfunction "A_A") (pintype "passive"))
    )
    (net (code "80") (name "Net-(LED75-C)") (class "Default")
      (node (ref "LED75") (pin "K") (pinfunction "C_K") (pintype "passive"))
      (node (ref "R25") (pin "2") (pinfunction "2_2") (pintype "passive"))
    )
    (net (code "81") (name "Net-(LED76-C)") (class "Default")
      (node (ref "LED76") (pin "K") (pinfunction "C_K") (pintype "passive"))
      (node (ref "R26") (pin "2") (pinfunction "2_2") (pintype "passive"))
    )
    (net (code "82") (name "Net-(LED77-C)") (class "Default")
      (node (ref "LED76") (pin "A") (pinfunction "A_A") (pintype "passive"))
      (node (ref "LED77") (pin "K") (pinfunction "C_K") (pintype "passive"))
    )
    (net (code "83") (name "Net-(LED78-C)") (class "Default")
      (node (ref "LED77") (pin "A") (pinfunction "A_A") (pintype "passive"))
      (node (ref "LED78") (pin "K") (pinfunction "C_K") (pintype "passive"))
    )
    (net (code "84") (name "Net-(LED79-C)") (class "Default")
      (node (ref "LED79") (pin "K") (pinfunction "C_K") (pintype "passive"))
      (node (ref "LED80") (pin "A") (pinfunction "A_A") (pintype "passive"))
    )
    (net (code "85") (name "Net-(LED80-C)") (class "Default")
      (node (ref "LED80") (pin "K") (pinfunction "C_K") (pintype "passive"))
      (node (ref "LED81") (pin "A") (pinfunction "A_A") (pintype "passive"))
    )
    (net (code "86") (name "Net-(LED81-C)") (class "Default")
      (node (ref "LED81") (pin "K") (pinfunction "C_K") (pintype "passive"))
      (node (ref "R27") (pin "2") (pinfunction "2_2") (pintype "passive"))
    )
    (net (code "87") (name "Net-(LED82-C)") (class "Default")
      (node (ref "LED82") (pin "K") (pinfunction "C_K") (pintype "passive"))
      (node (ref "LED83") (pin "A") (pinfunction "A_A") (pintype "passive"))
    )
    (net (code "88") (name "Net-(LED83-C)") (class "Default")
      (node (ref "LED83") (pin "K") (pinfunction "C_K") (pintype "passive"))
      (node (ref "LED84") (pin "A") (pinfunction "A_A") (pintype "passive"))
    )
    (net (code "89") (name "Net-(LED84-C)") (class "Default")
      (node (ref "LED84") (pin "K") (pinfunction "C_K") (pintype "passive"))
      (node (ref "R28") (pin "2") (pinfunction "2_2") (pintype "passive"))
    )
    (net (code "90") (name "Net-(LED85-C)") (class "Default")
      (node (ref "LED85") (pin "K") (pinfunction "C_K") (pintype "passive"))
      (node (ref "LED86") (pin "A") (pinfunction "A_A") (pintype "passive"))
    )
    (net (code "91") (name "Net-(LED86-C)") (class "Default")
      (node (ref "LED86") (pin "K") (pinfunction "C_K") (pintype "passive"))
      (node (ref "LED87") (pin "A") (pinfunction "A_A") (pintype "passive"))
    )
    (net (code "92") (name "Net-(LED87-C)") (class "Default")
      (node (ref "LED87") (pin "K") (pinfunction "C_K") (pintype "passive"))
      (node (ref "R29") (pin "2") (pinfunction "2_2") (pintype "passive"))
    )
    (net (code "93") (name "Net-(LED88-C)") (class "Default")
      (node (ref "LED88") (pin "K") (pinfunction "C_K") (pintype "passive"))
      (node (ref "LED89") (pin "A") (pinfunction "A_A") (pintype "passive"))
    )
    (net (code "94") (name "Net-(LED89-C)") (class "Default")
      (node (ref "LED89") (pin "K") (pinfunction "C_K") (pintype "passive"))
      (node (ref "LED90") (pin "A") (pinfunction "A_A") (pintype "passive"))
    )
    (net (code "95") (name "Net-(LED90-C)") (class "Default")
      (node (ref "LED90") (pin "K") (pinfunction "C_K") (pintype "passive"))
      (node (ref "R30") (pin "2") (pinfunction "2_2") (pintype "passive"))
    )
    (net (code "96") (name "Net-(LED91-C)") (class "Default")
      (node (ref "LED91") (pin "K") (pinfunction "C_K") (pintype "passive"))
      (node (ref "LED92") (pin "A") (pinfunction "A_A") (pintype "passive"))
    )
    (net (code "97") (name "Net-(LED92-C)") (class "Default")
      (node (ref "LED92") (pin "K") (pinfunction "C_K") (pintype "passive"))
      (node (ref "LED93") (pin "A") (pinfunction "A_A") (pintype "passive"))
    )
    (net (code "98") (name "Net-(LED93-C)") (class "Default")
      (node (ref "LED93") (pin "K") (pinfunction "C_K") (pintype "passive"))
      (node (ref "R31") (pin "2") (pinfunction "2_2") (pintype "passive"))
    )
    (net (code "99") (name "Net-(LED94-C)") (class "Default")
      (node (ref "LED94") (pin "K") (pinfunction "C_K") (pintype "passive"))
      (node (ref "LED95") (pin "A") (pinfunction "A_A") (pintype "passive"))
    )
    (net (code "100") (name "Net-(LED95-C)") (class "Default")
      (node (ref "LED95") (pin "K") (pinfunction "C_K") (pintype "passive"))
      (node (ref "LED96") (pin "A") (pinfunction "A_A") (pintype "passive"))
    )
    (net (code "101") (name "Net-(LED96-C)") (class "Default")
      (node (ref "LED96") (pin "K") (pinfunction "C_K") (pintype "passive"))
      (node (ref "R32") (pin "2") (pinfunction "2_2") (pintype "passive"))
    )
    (net (code "102") (name "Net-(LED97-C)") (class "Default")
      (node (ref "LED97") (pin "K") (pinfunction "C_K") (pintype "passive"))
      (node (ref "LED98") (pin "A") (pinfunction "A_A") (pintype "passive"))
    )
    (net (code "103") (name "Net-(LED98-C)") (class "Default")
      (node (ref "LED98") (pin "K") (pinfunction "C_K") (pintype "passive"))
      (node (ref "LED99") (pin "A") (pinfunction "A_A") (pintype "passive"))
    )
    (net (code "104") (name "Net-(LED99-C)") (class "Default")
      (node (ref "LED99") (pin "K") (pinfunction "C_K") (pintype "passive"))
      (node (ref "R33") (pin "2") (pinfunction "2_2") (pintype "passive"))
    )
    (net (code "105") (name "Net-(LED100-C)") (class "Default")
      (node (ref "LED100") (pin "K") (pinfunction "C_K") (pintype "passive"))
      (node (ref "LED101") (pin "A") (pinfunction "A_A") (pintype "passive"))
    )
    (net (code "106") (name "Net-(LED101-C)") (class "Default")
      (node (ref "LED101") (pin "K") (pinfunction "C_K") (pintype "passive"))
      (node (ref "LED102") (pin "A") (pinfunction "A_A") (pintype "passive"))
    )
    (net (code "107") (name "Net-(LED102-C)") (class "Default")
      (node (ref "LED102") (pin "K") (pinfunction "C_K") (pintype "passive"))
      (node (ref "R34") (pin "2") (pinfunction "2_2") (pintype "passive"))
    )
    (net (code "108") (name "Net-(LED103-C)") (class "Default")
      (node (ref "LED103") (pin "K") (pinfunction "C_K") (pintype "passive"))
      (node (ref "LED104") (pin "A") (pinfunction "A_A") (pintype "passive"))
    )
    (net (code "109") (name "Net-(LED104-C)") (class "Default")
      (node (ref "LED104") (pin "K") (pinfunction "C_K") (pintype "passive"))
      (node (ref "LED105") (pin "A") (pinfunction "A_A") (pintype "passive"))
    )
    (net (code "110") (name "Net-(LED105-C)") (class "Default")
      (node (ref "LED105") (pin "K") (pinfunction "C_K") (pintype "passive"))
      (node (ref "R35") (pin "2") (pinfunction "2_2") (pintype "passive"))
    )
    (net (code "111") (name "Net-(LED106-C)") (class "Default")
      (node (ref "LED106") (pin "K") (pinfunction "C_K") (pintype "passive"))
      (node (ref "LED107") (pin "A") (pinfunction "A_A") (pintype "passive"))
    )
    (net (code "112") (name "Net-(LED107-C)") (class "Default")
      (node (ref "LED107") (pin "K") (pinfunction "C_K") (pintype "passive"))
      (node (ref "LED108") (pin "A") (pinfunction "A_A") (pintype "passive"))
    )
    (net (code "113") (name "Net-(LED108-C)") (class "Default")
      (node (ref "LED108") (pin "K") (pinfunction "C_K") (pintype "passive"))
      (node (ref "R36") (pin "2") (pinfunction "2_2") (pintype "passive"))
    )
    (net (code "114") (name "Net-(LED109-C)") (class "Default")
      (node (ref "LED109") (pin "K") (pinfunction "C_K") (pintype "passive"))
      (node (ref "LED110") (pin "A") (pinfunction "A_A") (pintype "passive"))
    )
    (net (code "115") (name "Net-(LED110-C)") (class "Default")
      (node (ref "LED110") (pin "K") (pinfunction "C_K") (pintype "passive"))
      (node (ref "LED111") (pin "A") (pinfunction "A_A") (pintype "passive"))
    )
    (net (code "116") (name "Net-(LED111-C)") (class "Default")
      (node (ref "LED111") (pin "K") (pinfunction "C_K") (pintype "passive"))
      (node (ref "R37") (pin "2") (pinfunction "2_2") (pintype "passive"))
    )
    (net (code "117") (name "Net-(LED112-C)") (class "Default")
      (node (ref "LED112") (pin "K") (pinfunction "C_K") (pintype "passive"))
      (node (ref "LED113") (pin "A") (pinfunction "A_A") (pintype "passive"))
    )
    (net (code "118") (name "Net-(LED113-C)") (class "Default")
      (node (ref "LED113") (pin "K") (pinfunction "C_K") (pintype "passive"))
      (node (ref "LED114") (pin "A") (pinfunction "A_A") (pintype "passive"))
    )
    (net (code "119") (name "Net-(LED114-C)") (class "Default")
      (node (ref "LED114") (pin "K") (pinfunction "C_K") (pintype "passive"))
      (node (ref "R38") (pin "2") (pinfunction "2_2") (pintype "passive"))
    )
    (net (code "120") (name "Net-(LED115-C)") (class "Default")
      (node (ref "LED115") (pin "K") (pinfunction "C_K") (pintype "passive"))
      (node (ref "LED116") (pin "A") (pinfunction "A_A") (pintype "passive"))
    )
    (net (code "121") (name "Net-(LED116-C)") (class "Default")
      (node (ref "LED116") (pin "K") (pinfunction "C_K") (pintype "passive"))
      (node (ref "LED117") (pin "A") (pinfunction "A_A") (pintype "passive"))
    )
    (net (code "122") (name "Net-(LED117-C)") (class "Default")
      (node (ref "LED117") (pin "K") (pinfunction "C_K") (pintype "passive"))
      (node (ref "R39") (pin "2") (pinfunction "2_2") (pintype "passive"))
    )
    (net (code "123") (name "Net-(LED118-C)") (class "Default")
      (node (ref "LED118") (pin "K") (pinfunction "C_K") (pintype "passive"))
      (node (ref "LED119") (pin "A") (pinfunction "A_A") (pintype "passive"))
    )
    (net (code "124") (name "Net-(LED119-C)") (class "Default")
      (node (ref "LED119") (pin "K") (pinfunction "C_K") (pintype "passive"))
      (node (ref "LED120") (pin "A") (pinfunction "A_A") (pintype "passive"))
    )
    (net (code "125") (name "Net-(LED120-C)") (class "Default")
      (node (ref "LED120") (pin "K") (pinfunction "C_K") (pintype "passive"))
      (node (ref "R40") (pin "2") (pinfunction "2_2") (pintype "passive"))
    )
    (net (code "126") (name "Net-(LED121-C)") (class "Default")
      (node (ref "LED121") (pin "K") (pinfunction "C_K") (pintype "passive"))
      (node (ref "LED122") (pin "A") (pinfunction "A_A") (pintype "passive"))
    )
    (net (code "127") (name "Net-(LED122-C)") (class "Default")
      (node (ref "LED122") (pin "K") (pinfunction "C_K") (pintype "passive"))
      (node (ref "LED123") (pin "A") (pinfunction "A_A") (pintype "passive"))
    )
    (net (code "128") (name "Net-(LED123-C)") (class "Default")
      (node (ref "LED123") (pin "K") (pinfunction "C_K") (pintype "passive"))
      (node (ref "R41") (pin "2") (pinfunction "2_2") (pintype "passive"))
    )
    (net (code "129") (name "Net-(LED124-C)") (class "Default")
      (node (ref "LED124") (pin "K") (pinfunction "C_K") (pintype "passive"))
      (node (ref "LED125") (pin "A") (pinfunction "A_A") (pintype "passive"))
    )
    (net (code "130") (name "Net-(LED125-C)") (class "Default")
      (node (ref "LED125") (pin "K") (pinfunction "C_K") (pintype "passive"))
      (node (ref "LED126") (pin "A") (pinfunction "A_A") (pintype "passive"))
    )
    (net (code "131") (name "Net-(LED126-C)") (class "Default")
      (node (ref "LED126") (pin "K") (pinfunction "C_K") (pintype "passive"))
      (node (ref "R42") (pin "2") (pinfunction "2_2") (pintype "passive"))
    )
    (net (code "132") (name "Net-(LED127-C)") (class "Default")
      (node (ref "LED127") (pin "K") (pinfunction "C_K") (pintype "passive"))
      (node (ref "LED128") (pin "A") (pinfunction "A_A") (pintype "passive"))
    )
    (net (code "133") (name "Net-(LED128-C)") (class "Default")
      (node (ref "LED128") (pin "K") (pinfunction "C_K") (pintype "passive"))
      (node (ref "R43") (pin "2") (pinfunction "2_2") (pintype "passive"))
    )
    (net (code "134") (name "Net-(LED129-C)") (class "Default")
      (node (ref "LED129") (pin "K") (pinfunction "C_K") (pintype "passive"))
      (node (ref "LED130") (pin "A") (pinfunction "A_A") (pintype "passive"))
    )
    (net (code "135") (name "Net-(LED130-C)") (class "Default")
      (node (ref "LED130") (pin "K") (pinfunction "C_K") (pintype "passive"))
      (node (ref "R44") (pin "2") (pinfunction "2_2") (pintype "passive"))
    )
    (net (code "136") (name "Net-(LED131-C)") (class "Default")
      (node (ref "LED131") (pin "K") (pinfunction "C_K") (pintype "passive"))
      (node (ref "LED132") (pin "A") (pinfunction "A_A") (pintype "passive"))
    )
    (net (code "137") (name "Net-(LED132-C)") (class "Default")
      (node (ref "LED132") (pin "K") (pinfunction "C_K") (pintype "passive"))
      (node (ref "R45") (pin "2") (pinfunction "2_2") (pintype "passive"))
    )
    (net (code "138") (name "Net-(LED133-C)") (class "Default")
      (node (ref "LED133") (pin "K") (pinfunction "C_K") (pintype "passive"))
      (node (ref "LED134") (pin "A") (pinfunction "A_A") (pintype "passive"))
    )
    (net (code "139") (name "Net-(LED134-C)") (class "Default")
      (node (ref "LED134") (pin "K") (pinfunction "C_K") (pintype "passive"))
      (node (ref "R46") (pin "2") (pinfunction "2_2") (pintype "passive"))
    )
    (net (code "140") (name "Net-(LED135-C)") (class "Default")
      (node (ref "LED135") (pin "K") (pinfunction "C_K") (pintype "passive"))
      (node (ref "LED136") (pin "A") (pinfunction "A_A") (pintype "passive"))
    )
    (net (code "141") (name "Net-(LED136-C)") (class "Default")
      (node (ref "LED136") (pin "K") (pinfunction "C_K") (pintype "passive"))
      (node (ref "R47") (pin "2") (pinfunction "2_2") (pintype "passive"))
    )
    (net (code "142") (name "Net-(LED137-C)") (class "Default")
      (node (ref "LED137") (pin "K") (pinfunction "C_K") (pintype "passive"))
      (node (ref "LED138") (pin "A") (pinfunction "A_A") (pintype "passive"))
    )
    (net (code "143") (name "Net-(LED138-C)") (class "Default")
      (node (ref "LED138") (pin "K") (pinfunction "C_K") (pintype "passive"))
      (node (ref "R48") (pin "2") (pinfunction "2_2") (pintype "passive"))
    )
    (net (code "144") (name "Net-(LED139-C)") (class "Default")
      (node (ref "LED139") (pin "K") (pinfunction "C_K") (pintype "passive"))
      (node (ref "LED140") (pin "A") (pinfunction "A_A") (pintype "passive"))
    )
    (net (code "145") (name "Net-(LED140-C)") (class "Default")
      (node (ref "LED140") (pin "K") (pinfunction "C_K") (pintype "passive"))
      (node (ref "R49") (pin "2") (pinfunction "2_2") (pintype "passive"))
    )
    (net (code "146") (name "Net-(LED141-C)") (class "Default")
      (node (ref "LED141") (pin "K") (pinfunction "C_K") (pintype "passive"))
      (node (ref "LED142") (pin "A") (pinfunction "A_A") (pintype "passive"))
    )
    (net (code "147") (name "Net-(LED142-C)") (class "Default")
      (node (ref "LED142") (pin "K") (pinfunction "C_K") (pintype "passive"))
      (node (ref "R50") (pin "2") (pinfunction "2_2") (pintype "passive"))
    )
    (net (code "148") (name "Net-(LED143-C)") (class "Default")
      (node (ref "LED143") (pin "K") (pinfunction "C_K") (pintype "passive"))
      (node (ref "LED144") (pin "A") (pinfunction "A_A") (pintype "passive"))
    )
    (net (code "149") (name "Net-(LED144-C)") (class "Default")
      (node (ref "LED144") (pin "K") (pinfunction "C_K") (pintype "passive"))
      (node (ref "R51") (pin "2") (pinfunction "2_2") (pintype "passive"))
    )
    (net (code "150") (name "Net-(LED145-C)") (class "Default")
      (node (ref "LED145") (pin "K") (pinfunction "C_K") (pintype "passive"))
      (node (ref "LED146") (pin "A") (pinfunction "A_A") (pintype "passive"))
    )
    (net (code "151") (name "Net-(LED146-C)") (class "Default")
      (node (ref "LED146") (pin "K") (pinfunction "C_K") (pintype "passive"))
      (node (ref "R52") (pin "2") (pinfunction "2_2") (pintype "passive"))
    )
    (net (code "152") (name "Net-(LED147-C)") (class "Default")
      (node (ref "LED147") (pin "K") (pinfunction "C_K") (pintype "passive"))
      (node (ref "LED148") (pin "A") (pinfunction "A_A") (pintype "passive"))
    )
    (net (code "153") (name "Net-(LED148-C)") (class "Default")
      (node (ref "LED148") (pin "K") (pinfunction "C_K") (pintype "passive"))
      (node (ref "R53") (pin "2") (pinfunction "2_2") (pintype "passive"))
    )
    (net (code "154") (name "Net-(LED149-C)") (class "Default")
      (node (ref "LED149") (pin "K") (pinfunction "C_K") (pintype "passive"))
      (node (ref "LED150") (pin "A") (pinfunction "A_A") (pintype "passive"))
    )
    (net (code "155") (name "Net-(LED150-C)") (class "Default")
      (node (ref "LED150") (pin "K") (pinfunction "C_K") (pintype "passive"))
      (node (ref "R54") (pin "2") (pinfunction "2_2") (pintype "passive"))
    )
    (net (code "156") (name "Net-(LED151-C)") (class "Default")
      (node (ref "LED151") (pin "K") (pinfunction "C_K") (pintype "passive"))
      (node (ref "LED152") (pin "A") (pinfunction "A_A") (pintype "passive"))
    )
    (net (code "157") (name "Net-(LED152-C)") (class "Default")
      (node (ref "LED152") (pin "K") (pinfunction "C_K") (pintype "passive"))
      (node (ref "R55") (pin "2") (pinfunction "2_2") (pintype "passive"))
    )
    (net (code "158") (name "Net-(LED153-C)") (class "Default")
      (node (ref "LED153") (pin "K") (pinfunction "C_K") (pintype "passive"))
      (node (ref "LED154") (pin "A") (pinfunction "A_A") (pintype "passive"))
    )
    (net (code "159") (name "Net-(LED154-C)") (class "Default")
      (node (ref "LED154") (pin "K") (pinfunction "C_K") (pintype "passive"))
      (node (ref "R56") (pin "2") (pinfunction "2_2") (pintype "passive"))
    )
    (net (code "160") (name "Net-(T1-D)") (class "Default")
      (node (ref "R29") (pin "1") (pinfunction "1_1") (pintype "passive"))
      (node (ref "R30") (pin "1") (pinfunction "1_1") (pintype "passive"))
      (node (ref "R31") (pin "1") (pinfunction "1_1") (pintype "passive"))
      (node (ref "R32") (pin "1") (pinfunction "1_1") (pintype "passive"))
      (node (ref "R33") (pin "1") (pinfunction "1_1") (pintype "passive"))
      (node (ref "R34") (pin "1") (pinfunction "1_1") (pintype "passive"))
      (node (ref "R35") (pin "1") (pinfunction "1_1") (pintype "passive"))
      (node (ref "R36") (pin "1") (pinfunction "1_1") (pintype "passive"))
      (node (ref "R37") (pin "1") (pinfunction "1_1") (pintype "passive"))
      (node (ref "R38") (pin "1") (pinfunction "1_1") (pintype "passive"))
      (node (ref "R39") (pin "1") (pinfunction "1_1") (pintype "passive"))
      (node (ref "R40") (pin "1") (pinfunction "1_1") (pintype "passive"))
      (node (ref "R41") (pin "1") (pinfunction "1_1") (pintype "passive"))
      (node (ref "R42") (pin "1") (pinfunction "1_1") (pintype "passive"))
      (node (ref "T1") (pin "1") (pinfunction "D_1") (pintype "passive"))
    )
    (net (code "161") (name "Net-(T1-S)") (class "Default")
      (node (ref "JP1") (pin "1") (pinfunction "1_1") (pintype "passive"))
      (node (ref "R57") (pin "1") (pinfunction "1_1") (pintype "passive"))
      (node (ref "T1") (pin "2") (pinfunction "S_2") (pintype "passive"))
      (node (ref "T2") (pin "2") (pinfunction "S_2") (pintype "passive"))
      (node (ref "T3") (pin "2") (pinfunction "S_2") (pintype "passive"))
      (node (ref "T4") (pin "2") (pinfunction "S_2") (pintype "passive"))
    )
    (net (code "162") (name "Net-(T2-D)") (class "Default")
      (node (ref "R43") (pin "1") (pinfunction "1_1") (pintype "passive"))
      (node (ref "R44") (pin "1") (pinfunction "1_1") (pintype "passive"))
      (node (ref "R45") (pin "1") (pinfunction "1_1") (pintype "passive"))
      (node (ref "R46") (pin "1") (pinfunction "1_1") (pintype "passive"))
      (node (ref "R47") (pin "1") (pinfunction "1_1") (pintype "passive"))
      (node (ref "R48") (pin "1") (pinfunction "1_1") (pintype "passive"))
      (node (ref "R49") (pin "1") (pinfunction "1_1") (pintype "passive"))
      (node (ref "R50") (pin "1") (pinfunction "1_1") (pintype "passive"))
      (node (ref "R51") (pin "1") (pinfunction "1_1") (pintype "passive"))
      (node (ref "R52") (pin "1") (pinfunction "1_1") (pintype "passive"))
      (node (ref "R53") (pin "1") (pinfunction "1_1") (pintype "passive"))
      (node (ref "R54") (pin "1") (pinfunction "1_1") (pintype "passive"))
      (node (ref "R55") (pin "1") (pinfunction "1_1") (pintype "passive"))
      (node (ref "R56") (pin "1") (pinfunction "1_1") (pintype "passive"))
      (node (ref "T2") (pin "1") (pinfunction "D_1") (pintype "passive"))
    )
    (net (code "163") (name "Net-(T2-G)") (class "Default")
      (node (ref "JP2") (pin "1") (pinfunction "1_1") (pintype "passive"))
      (node (ref "T2") (pin "3") (pinfunction "G_3") (pintype "passive"))
    )
    (net (code "164") (name "Net-(T3-D)") (class "Default")
      (node (ref "R15") (pin "1") (pinfunction "1_1") (pintype "passive"))
      (node (ref "R16") (pin "1") (pinfunction "1_1") (pintype "passive"))
      (node (ref "R17") (pin "1") (pinfunction "1_1") (pintype "passive"))
      (node (ref "R18") (pin "1") (pinfunction "1_1") (pintype "passive"))
      (node (ref "R19") (pin "1") (pinfunction "1_1") (pintype "passive"))
      (node (ref "R20") (pin "1") (pinfunction "1_1") (pintype "passive"))
      (node (ref "R21") (pin "1") (pinfunction "1_1") (pintype "passive"))
      (node (ref "R22") (pin "1") (pinfunction "1_1") (pintype "passive"))
      (node (ref "R23") (pin "1") (pinfunction "1_1") (pintype "passive"))
      (node (ref "R24") (pin "1") (pinfunction "1_1") (pintype "passive"))
      (node (ref "R25") (pin "1") (pinfunction "1_1") (pintype "passive"))
      (node (ref "R26") (pin "1") (pinfunction "1_1") (pintype "passive"))
      (node (ref "R27") (pin "1") (pinfunction "1_1") (pintype "passive"))
      (node (ref "R28") (pin "1") (pinfunction "1_1") (pintype "passive"))
      (node (ref "T3") (pin "1") (pinfunction "D_1") (pintype "passive"))
    )
    (net (code "165") (name "Net-(T3-G)") (class "Default")
      (node (ref "JP2") (pin "2") (pinfunction "2_2") (pintype "passive"))
      (node (ref "T3") (pin "3") (pinfunction "G_3") (pintype "passive"))
    )
    (net (code "166") (name "Net-(T4-D)") (class "Default")
      (node (ref "R1") (pin "1") (pinfunction "1_1") (pintype "passive"))
      (node (ref "R10") (pin "1") (pinfunction "1_1") (pintype "passive"))
      (node (ref "R11") (pin "1") (pinfunction "1_1") (pintype "passive"))
      (node (ref "R12") (pin "1") (pinfunction "1_1") (pintype "passive"))
      (node (ref "R13") (pin "1") (pinfunction "1_1") (pintype "passive"))
      (node (ref "R14") (pin "1") (pinfunction "1_1") (pintype "passive"))
      (node (ref "R2") (pin "1") (pinfunction "1_1") (pintype "passive"))
      (node (ref "R3") (pin "1") (pinfunction "1_1") (pintype "passive"))
      (node (ref "R4") (pin "1") (pinfunction "1_1") (pintype "passive"))
      (node (ref "R5") (pin "1") (pinfunction "1_1") (pintype "passive"))
      (node (ref "R6") (pin "1") (pinfunction "1_1") (pintype "passive"))
      (node (ref "R7") (pin "1") (pinfunction "1_1") (pintype "passive"))
      (node (ref "R8") (pin "1") (pinfunction "1_1") (pintype "passive"))
      (node (ref "R9") (pin "1") (pinfunction "1_1") (pintype "passive"))
      (node (ref "T4") (pin "1") (pinfunction "D_1") (pintype "passive"))
    )
    (net (code "167") (name "unconnected-(JP2C-2-Pad6)") (class "Default")
      (node (ref "JP2") (pin "6") (pinfunction "2_6") (pintype "passive"))
    )
  )
)
